# GC.net
KiCad netlist of a schematic drawn in EAGLE
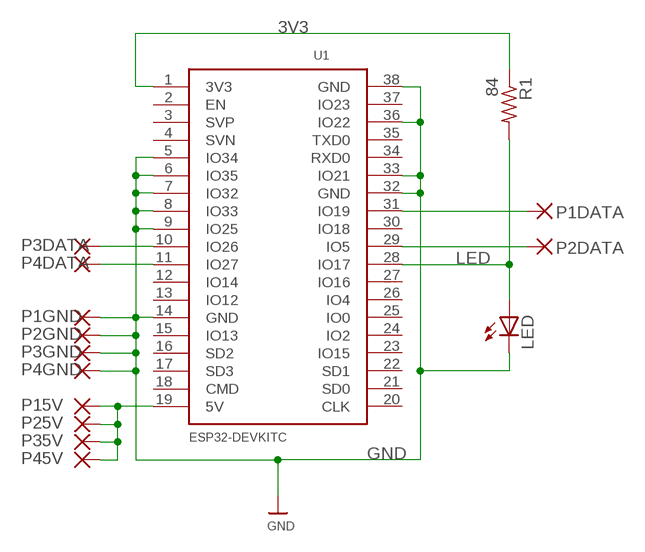
[diagram p0: schematic, sheet 1]

(export (version "E")
  (design (tool "Eeschema 10.0.6"))
  (components
    (comp (ref "LED")
      (value "LEDCHIPLED_1206")
      (footprint "eagle-import:CHIPLED_1206")
      (libsource (lib "eagle-import") (part "LEDCHIPLED_1206"))
    )
    (comp (ref "P1DATA")
      (value "SMD5")
      (footprint "eagle-import:SMD2,54-5,08")
      (libsource (lib "eagle-import") (part "SMD5"))
    )
    (comp (ref "P1GND")
      (value "SMD5")
      (footprint "eagle-import:SMD2,54-5,08")
      (libsource (lib "eagle-import") (part "SMD5"))
    )
    (comp (ref "P2DATA")
      (value "SMD5")
      (footprint "eagle-import:SMD2,54-5,08")
      (libsource (lib "eagle-import") (part "SMD5"))
    )
    (comp (ref "P2GND")
      (value "SMD5")
      (footprint "eagle-import:SMD2,54-5,08")
      (libsource (lib "eagle-import") (part "SMD5"))
    )
    (comp (ref "P3DATA")
      (value "SMD5")
      (footprint "eagle-import:SMD2,54-5,08")
      (libsource (lib "eagle-import") (part "SMD5"))
    )
    (comp (ref "P3GND")
      (value "SMD5")
      (footprint "eagle-import:SMD2,54-5,08")
      (libsource (lib "eagle-import") (part "SMD5"))
    )
    (comp (ref "P4DATA")
      (value "SMD5")
      (footprint "eagle-import:SMD2,54-5,08")
      (libsource (lib "eagle-import") (part "SMD5"))
    )
    (comp (ref "P4GND")
      (value "SMD5")
      (footprint "eagle-import:SMD2,54-5,08")
      (libsource (lib "eagle-import") (part "SMD5"))
    )
    (comp (ref "P15V")
      (value "SMD5")
      (footprint "eagle-import:SMD2,54-5,08")
      (libsource (lib "eagle-import") (part "SMD5"))
    )
    (comp (ref "P25V")
      (value "SMD5")
      (footprint "eagle-import:SMD2,54-5,08")
      (libsource (lib "eagle-import") (part "SMD5"))
    )
    (comp (ref "P35V")
      (value "SMD5")
      (footprint "eagle-import:SMD2,54-5,08")
      (libsource (lib "eagle-import") (part "SMD5"))
    )
    (comp (ref "P45V")
      (value "SMD5")
      (footprint "eagle-import:SMD2,54-5,08")
      (libsource (lib "eagle-import") (part "SMD5"))
    )
    (comp (ref "R1")
      (value "84")
      (footprint "eagle-import:R1206")
      (libsource (lib "eagle-import") (part "R-US_R1206"))
    )
    (comp (ref "U1")
      (value "ESP32DEVKITC")
      (footprint "eagle-import:ESP32-DEVKITC")
      (libsource (lib "eagle-import") (part "ESP32DEVKITC"))
    )
  )
  (nets
    (net (code "1") (name "/3V3") (class "Default")
      (node (ref "R1") (pin "1") (pinfunction "1_1") (pintype "passive"))
      (node (ref "U1") (pin "1") (pinfunction "3V3_1") (pintype "bidirectional"))
    )
    (net (code "2") (name "/LED") (class "Default")
      (node (ref "LED") (pin "A") (pinfunction "A_A") (pintype "passive"))
      (node (ref "R1") (pin "2") (pinfunction "2_2") (pintype "passive"))
      (node (ref "U1") (pin "28") (pinfunction "IO17_28") (pintype "bidirectional"))
    )
    (net (code "3") (name "GND") (class "Default")
      (node (ref "LED") (pin "C") (pinfunction "C_C") (pintype "passive"))
      (node (ref "P1GND") (pin "1") (pinfunction "P_1") (pintype "passive"))
      (node (ref "P2GND") (pin "1") (pinfunction "P_1") (pintype "passive"))
      (node (ref "P3GND") (pin "1") (pinfunction "P_1") (pintype "passive"))
      (node (ref "P4GND") (pin "1") (pinfunction "P_1") (pintype "passive"))
      (node (ref "U1") (pin "14") (pinfunction "GND_14") (pintype "bidirectional"))
      (node (ref "U1") (pin "32") (pinfunction "GND_32") (pintype "bidirectional"))
      (node (ref "U1") (pin "33") (pinfunction "IO21_33") (pintype "bidirectional"))
      (node (ref "U1") (pin "36") (pinfunction "IO22_36") (pintype "bidirectional"))
      (node (ref "U1") (pin "38") (pinfunction "GND_38") (pintype "bidirectional"))
      (node (ref "U1") (pin "5") (pinfunction "IO34_5") (pintype "bidirectional"))
      (node (ref "U1") (pin "6") (pinfunction "IO35_6") (pintype "bidirectional"))
      (node (ref "U1") (pin "7") (pinfunction "IO32_7") (pintype "bidirectional"))
      (node (ref "U1") (pin "8") (pinfunction "IO33_8") (pintype "bidirectional"))
      (node (ref "U1") (pin "9") (pinfunction "IO25_9") (pintype "bidirectional"))
    )
    (net (code "4") (name "Net-(P1DATA-P)") (class "Default")
      (node (ref "P1DATA") (pin "1") (pinfunction "P_1") (pintype "passive"))
      (node (ref "U1") (pin "31") (pinfunction "IO19_31") (pintype "bidirectional"))
    )
    (net (code "5") (name "Net-(P2DATA-P)") (class "Default")
      (node (ref "P2DATA") (pin "1") (pinfunction "P_1") (pintype "passive"))
      (node (ref "U1") (pin "29") (pinfunction "IO5_29") (pintype "bidirectional"))
    )
    (net (code "6") (name "Net-(P3DATA-P)") (class "Default")
      (node (ref "P3DATA") (pin "1") (pinfunction "P_1") (pintype "passive"))
      (node (ref "U1") (pin "10") (pinfunction "IO26_10") (pintype "bidirectional"))
    )
    (net (code "7") (name "Net-(P4DATA-P)") (class "Default")
      (node (ref "P4DATA") (pin "1") (pinfunction "P_1") (pintype "passive"))
      (node (ref "U1") (pin "11") (pinfunction "IO27_11") (pintype "bidirectional"))
    )
    (net (code "8") (name "Net-(P15V-P)") (class "Default")
      (node (ref "P15V") (pin "1") (pinfunction "P_1") (pintype "passive"))
      (node (ref "P25V") (pin "1") (pinfunction "P_1") (pintype "passive"))
      (node (ref "P35V") (pin "1") (pinfunction "P_1") (pintype "passive"))
      (node (ref "P45V") (pin "1") (pinfunction "P_1") (pintype "passive"))
      (node (ref "U1") (pin "19") (pinfunction "5V_19") (pintype "bidirectional"))
    )
    (net (code "9") (name "unconnected-(U1-CLK-Pad20)") (class "Default")
      (node (ref "U1") (pin "20") (pinfunction "CLK_20") (pintype "bidirectional"))
    )
    (net (code "10") (name "unconnected-(U1-CMD-Pad18)") (class "Default")
      (node (ref "U1") (pin "18") (pinfunction "CMD_18") (pintype "bidirectional"))
    )
    (net (code "11") (name "unconnected-(U1-EN-Pad2)") (class "Default")
      (node (ref "U1") (pin "2") (pinfunction "EN_2") (pintype "bidirectional"))
    )
    (net (code "12") (name "unconnected-(U1-IO0-Pad25)") (class "Default")
      (node (ref "U1") (pin "25") (pinfunction "IO0_25") (pintype "bidirectional"))
    )
    (net (code "13") (name "unconnected-(U1-IO2-Pad24)") (class "Default")
      (node (ref "U1") (pin "24") (pinfunction "IO2_24") (pintype "bidirectional"))
    )
    (net (code "14") (name "unconnected-(U1-IO4-Pad26)") (class "Default")
      (node (ref "U1") (pin "26") (pinfunction "IO4_26") (pintype "bidirectional"))
    )
    (net (code "15") (name "unconnected-(U1-IO12-Pad13)") (class "Default")
      (node (ref "U1") (pin "13") (pinfunction "IO12_13") (pintype "bidirectional"))
    )
    (net (code "16") (name "unconnected-(U1-IO13-Pad15)") (class "Default")
      (node (ref "U1") (pin "15") (pinfunction "IO13_15") (pintype "bidirectional"))
    )
    (net (code "17") (name "unconnected-(U1-IO14-Pad12)") (class "Default")
      (node (ref "U1") (pin "12") (pinfunction "IO14_12") (pintype "bidirectional"))
    )
    (net (code "18") (name "unconnected-(U1-IO15-Pad23)") (class "Default")
      (node (ref "U1") (pin "23") (pinfunction "IO15_23") (pintype "bidirectional"))
    )
    (net (code "19") (name "unconnected-(U1-IO16-Pad27)") (class "Default")
      (node (ref "U1") (pin "27") (pinfunction "IO16_27") (pintype "bidirectional"))
    )
    (net (code "20") (name "unconnected-(U1-IO18-Pad30)") (class "Default")
      (node (ref "U1") (pin "30") (pinfunction "IO18_30") (pintype "bidirectional"))
    )
    (net (code "21") (name "unconnected-(U1-IO23-Pad37)") (class "Default")
      (node (ref "U1") (pin "37") (pinfunction "IO23_37") (pintype "bidirectional"))
    )
    (net (code "22") (name "unconnected-(U1-RXD0-Pad34)") (class "Default")
      (node (ref "U1") (pin "34") (pinfunction "RXD0_34") (pintype "bidirectional"))
    )
    (net (code "23") (name "unconnected-(U1-SD0-Pad21)") (class "Default")
      (node (ref "U1") (pin "21") (pinfunction "SD0_21") (pintype "bidirectional"))
    )
    (net (code "24") (name "unconnected-(U1-SD1-Pad22)") (class "Default")
      (node (ref "U1") (pin "22") (pinfunction "SD1_22") (pintype "bidirectional"))
    )
    (net (code "25") (name "unconnected-(U1-SD2-Pad16)") (class "Default")
      (node (ref "U1") (pin "16") (pinfunction "SD2_16") (pintype "bidirectional"))
    )
    (net (code "26") (name "unconnected-(U1-SD3-Pad17)") (class "Default")
      (node (ref "U1") (pin "17") (pinfunction "SD3_17") (pintype "bidirectional"))
    )
    (net (code "27") (name "unconnected-(U1-SVN-Pad4)") (class "Default")
      (node (ref "U1") (pin "4") (pinfunction "SVN_4") (pintype "bidirectional"))
    )
    (net (code "28") (name "unconnected-(U1-SVP-Pad3)") (class "Default")
      (node (ref "U1") (pin "3") (pinfunction "SVP_3") (pintype "bidirectional"))
    )
    (net (code "29") (name "unconnected-(U1-TXD0-Pad35)") (class "Default")
      (node (ref "U1") (pin "35") (pinfunction "TXD0_35") (pintype "bidirectional"))
    )
  )
)
